# DC_Sensor_ESP8266_ADC_NC_11b.net
KiCad netlist of a schematic drawn in EAGLE
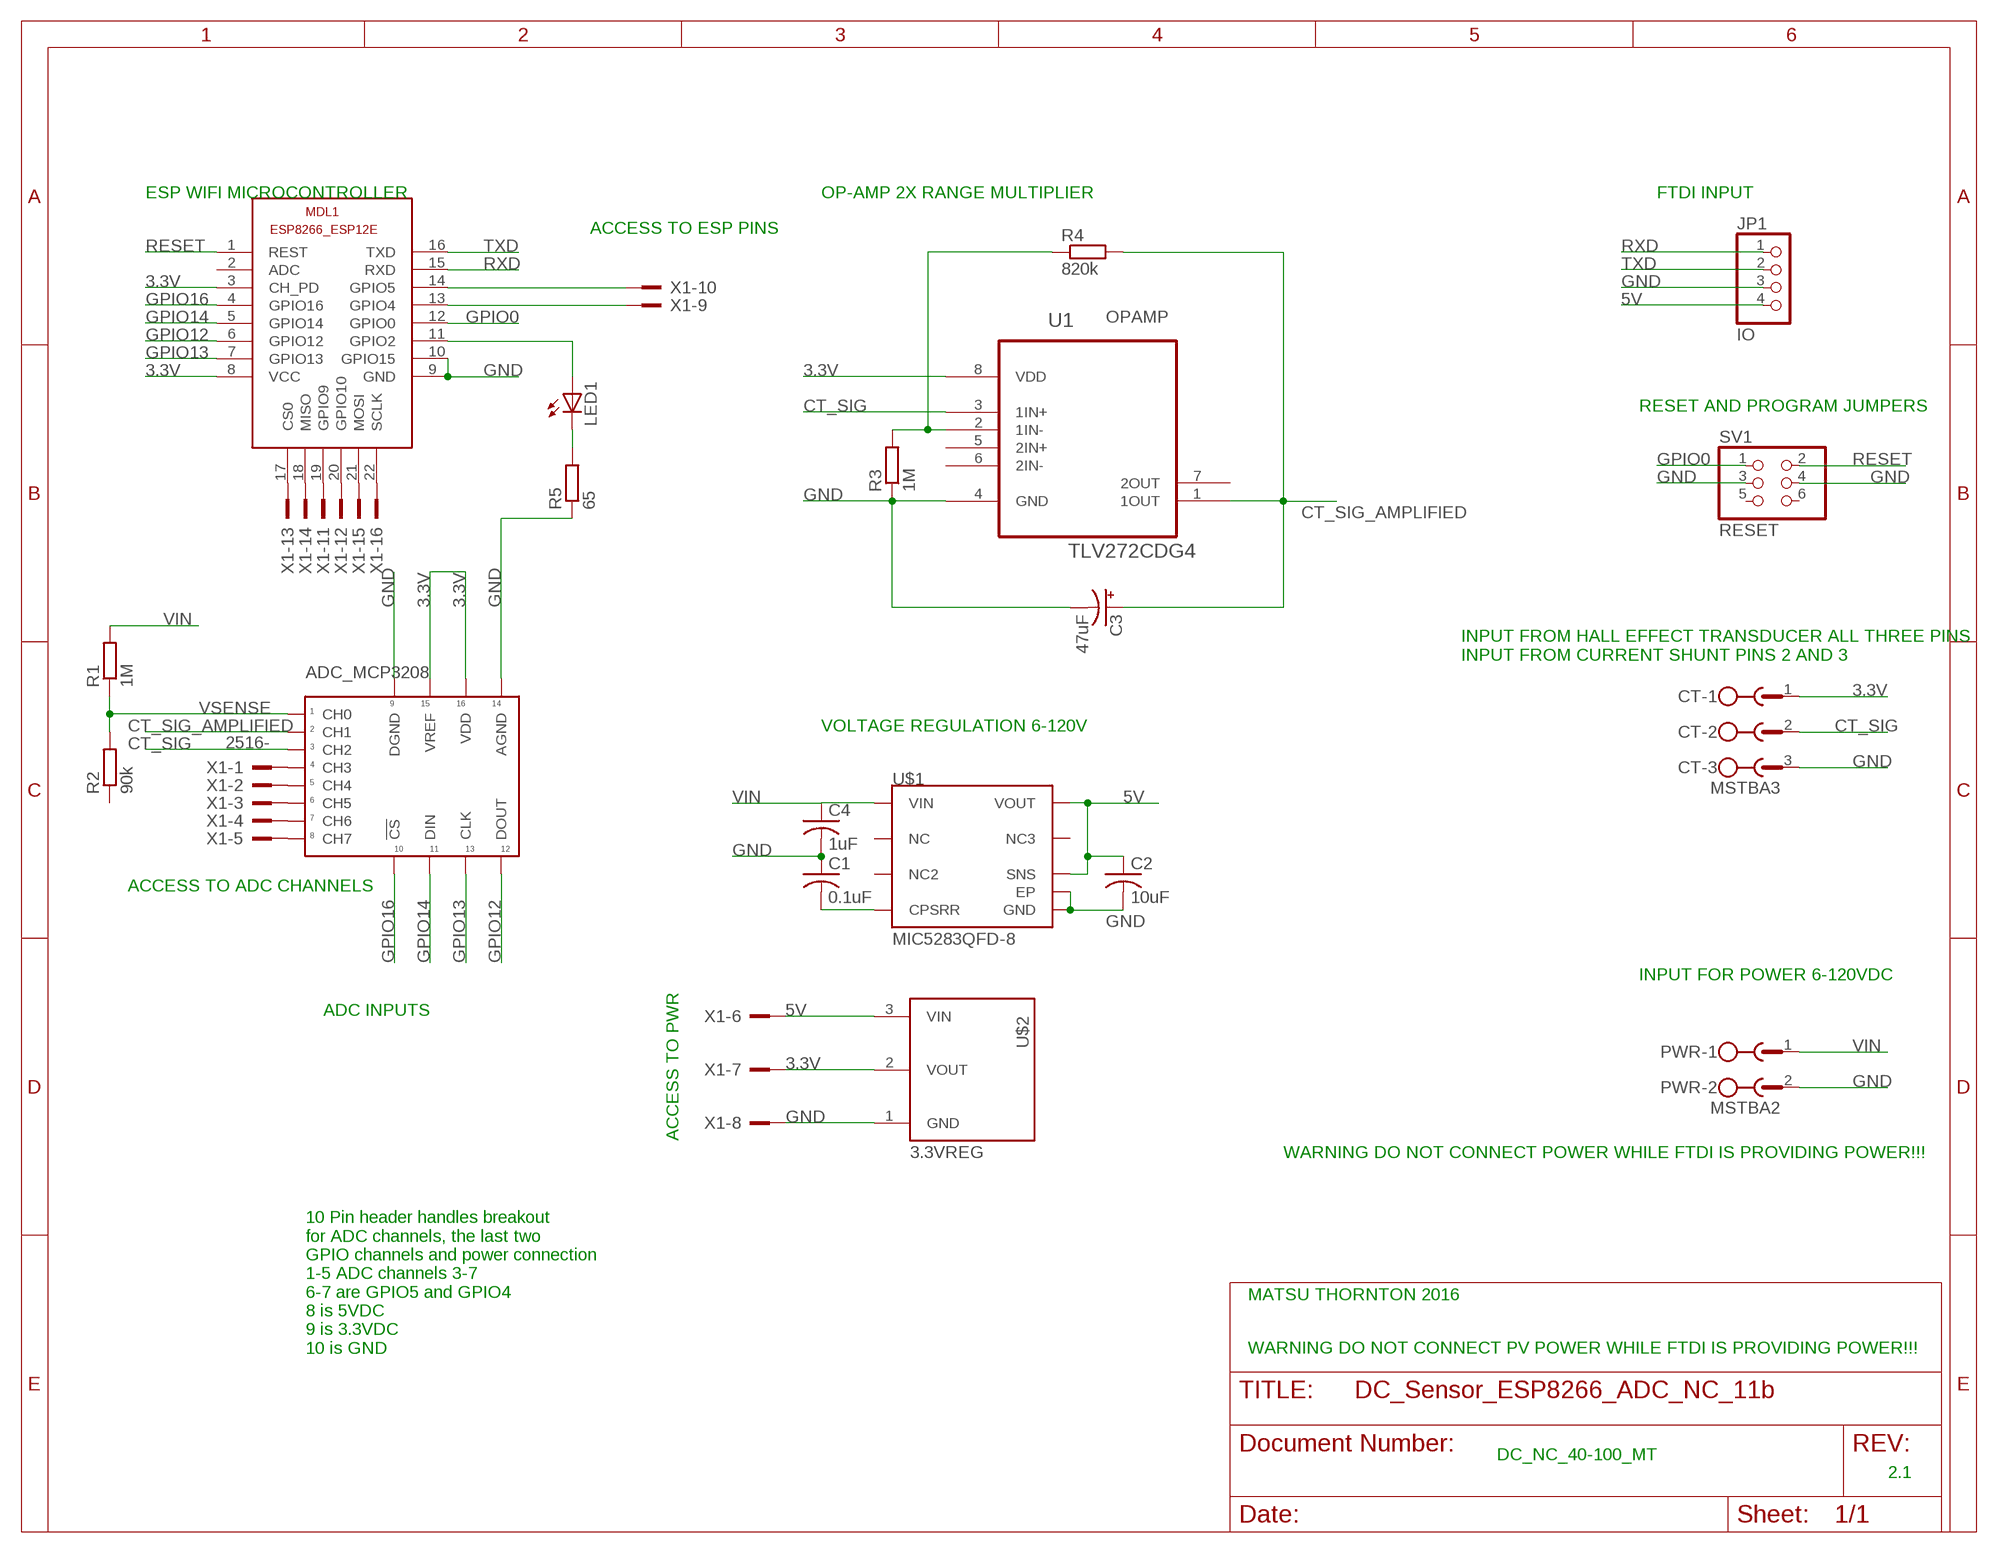
[diagram p0: schematic, sheet 1]

(export (version "E")
  (design (tool "Eeschema 10.0.6"))
  (components
    (comp (ref "ADC_MCP3208")
      (value "21298ESMD")
      (footprint "eagle-import:PDIP16")
      (libsource (lib "eagle-import") (part "21298ESMD"))
    )
    (comp (ref "C1")
      (value "0.1uF")
      (footprint "eagle-import:C0402")
      (libsource (lib "eagle-import") (part "C-USC0402"))
    )
    (comp (ref "C2")
      (value "10uF")
      (footprint "eagle-import:C0603K")
      (libsource (lib "eagle-import") (part "C-USC0603K"))
    )
    (comp (ref "C3")
      (value "47uF")
      (footprint "eagle-import:PANASONIC_C")
      (libsource (lib "eagle-import") (part "CPOL-USC"))
    )
    (comp (ref "C4")
      (value "1uF")
      (footprint "eagle-import:C2220K")
      (libsource (lib "eagle-import") (part "C-USC2220K"))
    )
    (comp (ref "CT")
      (value "MSTBA3")
      (footprint "eagle-import:MSTBA3")
      (fields (field (name "MF") "FARNELL") (field (name "MPN") "1757255"))
      (libsource (lib "eagle-import") (part "MSTBA3"))
    )
    (comp (ref "JP1")
      (value "IO")
      (footprint "eagle-import:1X04")
      (libsource (lib "eagle-import") (part "PINHD-1X4"))
    )
    (comp (ref "LED1")
      (value "LEDCHIP-LED0603")
      (footprint "eagle-import:CHIP-LED0603")
      (libsource (lib "eagle-import") (part "LEDCHIP-LED0603"))
    )
    (comp (ref "MDL1")
      (value "ESP8266-12EESP8266-ESP12E")
      (footprint "eagle-import:ESP8266-ESP12E")
      (libsource (lib "eagle-import") (part "ESP8266-12EESP8266-ESP12E"))
    )
    (comp (ref "PWR")
      (value "MSTBA2")
      (footprint "eagle-import:MSTBA2")
      (fields (field (name "MF") "FARNELL") (field (name "MPN") "1757242"))
      (libsource (lib "eagle-import") (part "MSTBA2"))
    )
    (comp (ref "R1")
      (value "1M")
      (footprint "eagle-import:R0805")
      (libsource (lib "eagle-import") (part "R-EU_R0805"))
    )
    (comp (ref "R2")
      (value "90k")
      (footprint "eagle-import:R0805")
      (libsource (lib "eagle-import") (part "R-EU_R0805"))
    )
    (comp (ref "R3")
      (value "1M")
      (footprint "eagle-import:R0805")
      (libsource (lib "eagle-import") (part "R-EU_R0805"))
    )
    (comp (ref "R4")
      (value "820k")
      (footprint "eagle-import:R0805")
      (libsource (lib "eagle-import") (part "R-EU_R0805"))
    )
    (comp (ref "R5")
      (value "65")
      (footprint "eagle-import:R0805")
      (libsource (lib "eagle-import") (part "R-EU_R0805"))
    )
    (comp (ref "SV1")
      (value "RESET")
      (footprint "eagle-import:2X03")
      (libsource (lib "eagle-import") (part "PINHD-2X3"))
    )
    (comp (ref "U$1")
      (value "MIC5283QFD-8")
      (footprint "eagle-import:8-VDFN")
      (libsource (lib "eagle-import") (part "MIC5283QFD-8"))
    )
    (comp (ref "U$2")
      (value "3.3VREG")
      (footprint "eagle-import:3PVREG")
      (libsource (lib "eagle-import") (part "3.3VREG"))
    )
    (comp (ref "U1")
      (value "TLV272CDG4")
      (footprint "eagle-import:SOIC127P600X175-8N")
      (fields (field (name "TYPE") "OPAMP"))
      (libsource (lib "eagle-import") (part "TLV272CDG4"))
    )
    (comp (ref "X1")
      (value "2516-")
      (footprint "eagle-import:PAK100_2500-16")
      (libsource (lib "eagle-import") (part "2516-"))
    )
  )
  (nets
    (net (code "1") (name "/3.3V") (class "Default")
      (node (ref "ADC_MCP3208") (pin "P$15") (pinfunction "VREF_P$15") (pintype "bidirectional"))
      (node (ref "ADC_MCP3208") (pin "P$16") (pinfunction "VDD_P$16") (pintype "bidirectional"))
      (node (ref "CT") (pin "1") (pinfunction "1_1") (pintype "passive"))
      (node (ref "MDL1") (pin "3") (pinfunction "CH_PD_3") (pintype "bidirectional"))
      (node (ref "MDL1") (pin "8") (pinfunction "VCC_8") (pintype "bidirectional"))
      (node (ref "U$2") (pin "2") (pinfunction "VOUT_2") (pintype "bidirectional"))
      (node (ref "U1") (pin "8") (pinfunction "VDD_8") (pintype "power_in"))
      (node (ref "X1") (pin "7") (pinfunction "KL_7") (pintype "passive"))
    )
    (net (code "2") (name "/5V") (class "Default")
      (node (ref "C2") (pin "1") (pinfunction "1_1") (pintype "passive"))
      (node (ref "JP1") (pin "4") (pinfunction "4_4") (pintype "passive"))
      (node (ref "U$1") (pin "P$6") (pinfunction "SNS_P$6") (pintype "input"))
      (node (ref "U$1") (pin "P$8") (pinfunction "VOUT_P$8") (pintype "output"))
      (node (ref "U$2") (pin "3") (pinfunction "VIN_3") (pintype "bidirectional"))
      (node (ref "X1") (pin "6") (pinfunction "KL_6") (pintype "passive"))
    )
    (net (code "3") (name "/CT_SIG") (class "Default")
      (node (ref "ADC_MCP3208") (pin "P$3") (pinfunction "CH2_P$3") (pintype "bidirectional"))
      (node (ref "CT") (pin "2") (pinfunction "1_2") (pintype "passive"))
      (node (ref "U1") (pin "3") (pinfunction "1IN+_3") (pintype "input"))
    )
    (net (code "4") (name "/CT_SIG_AMPLIFIED") (class "Default")
      (node (ref "ADC_MCP3208") (pin "P$2") (pinfunction "CH1_P$2") (pintype "bidirectional"))
      (node (ref "C3") (pin "+") (pinfunction "+_+") (pintype "passive"))
      (node (ref "R4") (pin "2") (pinfunction "2_2") (pintype "passive"))
      (node (ref "U1") (pin "1") (pinfunction "1OUT_1") (pintype "output"))
    )
    (net (code "5") (name "/GND") (class "Default")
      (node (ref "ADC_MCP3208") (pin "P$14") (pinfunction "AGND_P$14") (pintype "bidirectional"))
      (node (ref "ADC_MCP3208") (pin "P$9") (pinfunction "DGND_P$9") (pintype "bidirectional"))
      (node (ref "C1") (pin "1") (pinfunction "1_1") (pintype "passive"))
      (node (ref "C2") (pin "2") (pinfunction "2_2") (pintype "passive"))
      (node (ref "C3") (pin "-") (pinfunction "-_-") (pintype "passive"))
      (node (ref "C4") (pin "2") (pinfunction "2_2") (pintype "passive"))
      (node (ref "CT") (pin "3") (pinfunction "1_3") (pintype "passive"))
      (node (ref "JP1") (pin "3") (pinfunction "3_3") (pintype "passive"))
      (node (ref "MDL1") (pin "10") (pinfunction "GPIO15_10") (pintype "bidirectional"))
      (node (ref "MDL1") (pin "9") (pinfunction "GND_9") (pintype "bidirectional"))
      (node (ref "PWR") (pin "2") (pinfunction "1_2") (pintype "passive"))
      (node (ref "R3") (pin "1") (pinfunction "1_1") (pintype "passive"))
      (node (ref "R5") (pin "1") (pinfunction "1_1") (pintype "passive"))
      (node (ref "SV1") (pin "3") (pinfunction "3_3") (pintype "passive"))
      (node (ref "SV1") (pin "4") (pinfunction "4_4") (pintype "passive"))
      (node (ref "U$1") (pin "EXP") (pinfunction "EP_EXP") (pintype "bidirectional"))
      (node (ref "U$1") (pin "P$5") (pinfunction "GND_P$5") (pintype "power_in"))
      (node (ref "U$2") (pin "1") (pinfunction "GND_1") (pintype "bidirectional"))
      (node (ref "U1") (pin "4") (pinfunction "GND_4") (pintype "passive"))
      (node (ref "X1") (pin "8") (pinfunction "KL_8") (pintype "passive"))
    )
    (net (code "6") (name "/GPIO0") (class "Default")
      (node (ref "MDL1") (pin "12") (pinfunction "GPIO0_12") (pintype "bidirectional"))
      (node (ref "SV1") (pin "1") (pinfunction "1_1") (pintype "passive"))
    )
    (net (code "7") (name "/GPIO12") (class "Default")
      (node (ref "ADC_MCP3208") (pin "P$12") (pinfunction "DOUT_P$12") (pintype "bidirectional"))
      (node (ref "MDL1") (pin "6") (pinfunction "GPIO12_6") (pintype "bidirectional"))
    )
    (net (code "8") (name "/GPIO13") (class "Default")
      (node (ref "ADC_MCP3208") (pin "P$13") (pinfunction "CLK_P$13") (pintype "bidirectional"))
      (node (ref "MDL1") (pin "7") (pinfunction "GPIO13_7") (pintype "bidirectional"))
    )
    (net (code "9") (name "/GPIO14") (class "Default")
      (node (ref "ADC_MCP3208") (pin "P$11") (pinfunction "DIN_P$11") (pintype "bidirectional"))
      (node (ref "MDL1") (pin "5") (pinfunction "GPIO14_5") (pintype "bidirectional"))
    )
    (net (code "10") (name "/GPIO16") (class "Default")
      (node (ref "ADC_MCP3208") (pin "P$10") (pinfunction "~{CS}_P$10") (pintype "bidirectional"))
      (node (ref "MDL1") (pin "4") (pinfunction "GPIO16_4") (pintype "bidirectional"))
    )
    (net (code "11") (name "/RESET") (class "Default")
      (node (ref "MDL1") (pin "1") (pinfunction "REST_1") (pintype "bidirectional"))
      (node (ref "SV1") (pin "2") (pinfunction "2_2") (pintype "passive"))
    )
    (net (code "12") (name "/RXD") (class "Default")
      (node (ref "JP1") (pin "1") (pinfunction "1_1") (pintype "passive"))
      (node (ref "MDL1") (pin "15") (pinfunction "RXD_15") (pintype "bidirectional"))
    )
    (net (code "13") (name "/TXD") (class "Default")
      (node (ref "JP1") (pin "2") (pinfunction "2_2") (pintype "passive"))
      (node (ref "MDL1") (pin "16") (pinfunction "TXD_16") (pintype "bidirectional"))
    )
    (net (code "14") (name "/VIN") (class "Default")
      (node (ref "C4") (pin "1") (pinfunction "1_1") (pintype "passive"))
      (node (ref "PWR") (pin "1") (pinfunction "1_1") (pintype "passive"))
      (node (ref "R1") (pin "2") (pinfunction "2_2") (pintype "passive"))
      (node (ref "U$1") (pin "P$1") (pinfunction "VIN_P$1") (pintype "input"))
    )
    (net (code "15") (name "/VSENSE") (class "Default")
      (node (ref "ADC_MCP3208") (pin "P$1") (pinfunction "CH0_P$1") (pintype "bidirectional"))
      (node (ref "R1") (pin "1") (pinfunction "1_1") (pintype "passive"))
      (node (ref "R2") (pin "2") (pinfunction "2_2") (pintype "passive"))
    )
    (net (code "16") (name "Net-(ADC_MCP3208-CH3)") (class "Default")
      (node (ref "ADC_MCP3208") (pin "P$4") (pinfunction "CH3_P$4") (pintype "bidirectional"))
      (node (ref "X1") (pin "1") (pinfunction "KL_1") (pintype "passive"))
    )
    (net (code "17") (name "Net-(ADC_MCP3208-CH4)") (class "Default")
      (node (ref "ADC_MCP3208") (pin "P$5") (pinfunction "CH4_P$5") (pintype "bidirectional"))
      (node (ref "X1") (pin "2") (pinfunction "KL_2") (pintype "passive"))
    )
    (net (code "18") (name "Net-(ADC_MCP3208-CH5)") (class "Default")
      (node (ref "ADC_MCP3208") (pin "P$6") (pinfunction "CH5_P$6") (pintype "bidirectional"))
      (node (ref "X1") (pin "3") (pinfunction "KL_3") (pintype "passive"))
    )
    (net (code "19") (name "Net-(ADC_MCP3208-CH6)") (class "Default")
      (node (ref "ADC_MCP3208") (pin "P$7") (pinfunction "CH6_P$7") (pintype "bidirectional"))
      (node (ref "X1") (pin "4") (pinfunction "KL_4") (pintype "passive"))
    )
    (net (code "20") (name "Net-(ADC_MCP3208-CH7)") (class "Default")
      (node (ref "ADC_MCP3208") (pin "P$8") (pinfunction "CH7_P$8") (pintype "bidirectional"))
      (node (ref "X1") (pin "5") (pinfunction "KL_5") (pintype "passive"))
    )
    (net (code "21") (name "Net-(LED1-PadC)") (class "Default")
      (node (ref "LED1") (pin "C") (pinfunction "C_C") (pintype "passive"))
      (node (ref "R5") (pin "2") (pinfunction "2_2") (pintype "passive"))
    )
    (net (code "22") (name "Net-(MDL1-CS0)") (class "Default")
      (node (ref "MDL1") (pin "17") (pinfunction "CS0_17") (pintype "bidirectional"))
      (node (ref "X1") (pin "13") (pinfunction "KL_13") (pintype "passive"))
    )
    (net (code "23") (name "Net-(MDL1-GPIO2)") (class "Default")
      (node (ref "LED1") (pin "A") (pinfunction "A_A") (pintype "passive"))
      (node (ref "MDL1") (pin "11") (pinfunction "GPIO2_11") (pintype "bidirectional"))
    )
    (net (code "24") (name "Net-(MDL1-GPIO4)") (class "Default")
      (node (ref "MDL1") (pin "13") (pinfunction "GPIO4_13") (pintype "bidirectional"))
      (node (ref "X1") (pin "9") (pinfunction "KL_9") (pintype "passive"))
    )
    (net (code "25") (name "Net-(MDL1-GPIO5)") (class "Default")
      (node (ref "MDL1") (pin "14") (pinfunction "GPIO5_14") (pintype "bidirectional"))
      (node (ref "X1") (pin "10") (pinfunction "KL_10") (pintype "passive"))
    )
    (net (code "26") (name "Net-(MDL1-GPIO9)") (class "Default")
      (node (ref "MDL1") (pin "19") (pinfunction "GPIO9_19") (pintype "bidirectional"))
      (node (ref "X1") (pin "11") (pinfunction "KL_11") (pintype "passive"))
    )
    (net (code "27") (name "Net-(MDL1-GPIO10)") (class "Default")
      (node (ref "MDL1") (pin "20") (pinfunction "GPIO10_20") (pintype "bidirectional"))
      (node (ref "X1") (pin "12") (pinfunction "KL_12") (pintype "passive"))
    )
    (net (code "28") (name "Net-(MDL1-MISO)") (class "Default")
      (node (ref "MDL1") (pin "18") (pinfunction "MISO_18") (pintype "bidirectional"))
      (node (ref "X1") (pin "14") (pinfunction "KL_14") (pintype "passive"))
    )
    (net (code "29") (name "Net-(MDL1-MOSI)") (class "Default")
      (node (ref "MDL1") (pin "21") (pinfunction "MOSI_21") (pintype "bidirectional"))
      (node (ref "X1") (pin "15") (pinfunction "KL_15") (pintype "passive"))
    )
    (net (code "30") (name "Net-(MDL1-SCLK)") (class "Default")
      (node (ref "MDL1") (pin "22") (pinfunction "SCLK_22") (pintype "bidirectional"))
      (node (ref "X1") (pin "16") (pinfunction "KL_16") (pintype "passive"))
    )
    (net (code "31") (name "Net-(U$1-CPSRR)") (class "Default")
      (node (ref "C1") (pin "2") (pinfunction "2_2") (pintype "passive"))
      (node (ref "U$1") (pin "P$4") (pinfunction "CPSRR_P$4") (pintype "input"))
    )
    (net (code "32") (name "Net-(U1-1IN-)") (class "Default")
      (node (ref "R3") (pin "2") (pinfunction "2_2") (pintype "passive"))
      (node (ref "R4") (pin "1") (pinfunction "1_1") (pintype "passive"))
      (node (ref "U1") (pin "2") (pinfunction "1IN-_2") (pintype "input"))
    )
    (net (code "33") (name "unconnected-(MDL1-ADC-Pad2)") (class "Default")
      (node (ref "MDL1") (pin "2") (pinfunction "ADC_2") (pintype "bidirectional"))
    )
    (net (code "34") (name "unconnected-(R2-Pad1)") (class "Default")
      (node (ref "R2") (pin "1") (pinfunction "1_1") (pintype "passive"))
    )
    (net (code "35") (name "unconnected-(SV1-Pad5)") (class "Default")
      (node (ref "SV1") (pin "5") (pinfunction "5_5") (pintype "passive"))
    )
    (net (code "36") (name "unconnected-(SV1-Pad6)") (class "Default")
      (node (ref "SV1") (pin "6") (pinfunction "6_6") (pintype "passive"))
    )
    (net (code "37") (name "unconnected-(U$1-NC-PadP$2)") (class "Default")
      (node (ref "U$1") (pin "P$2") (pinfunction "NC_P$2") (pintype "input"))
    )
    (net (code "38") (name "unconnected-(U$1-NC2-PadP$3)") (class "Default")
      (node (ref "U$1") (pin "P$3") (pinfunction "NC2_P$3") (pintype "input"))
    )
    (net (code "39") (name "unconnected-(U$1-NC3-PadP$7)") (class "Default")
      (node (ref "U$1") (pin "P$7") (pinfunction "NC3_P$7") (pintype "output"))
    )
    (net (code "40") (name "unconnected-(U1-2IN+-Pad5)") (class "Default")
      (node (ref "U1") (pin "5") (pinfunction "2IN+_5") (pintype "input"))
    )
    (net (code "41") (name "unconnected-(U1-2IN--Pad6)") (class "Default")
      (node (ref "U1") (pin "6") (pinfunction "2IN-_6") (pintype "input"))
    )
    (net (code "42") (name "unconnected-(U1-2OUT-Pad7)") (class "Default")
      (node (ref "U1") (pin "7") (pinfunction "2OUT_7") (pintype "output"))
    )
  )
)
